# Opticalpulsesensor1.net
KiCad netlist of a schematic drawn in EAGLE
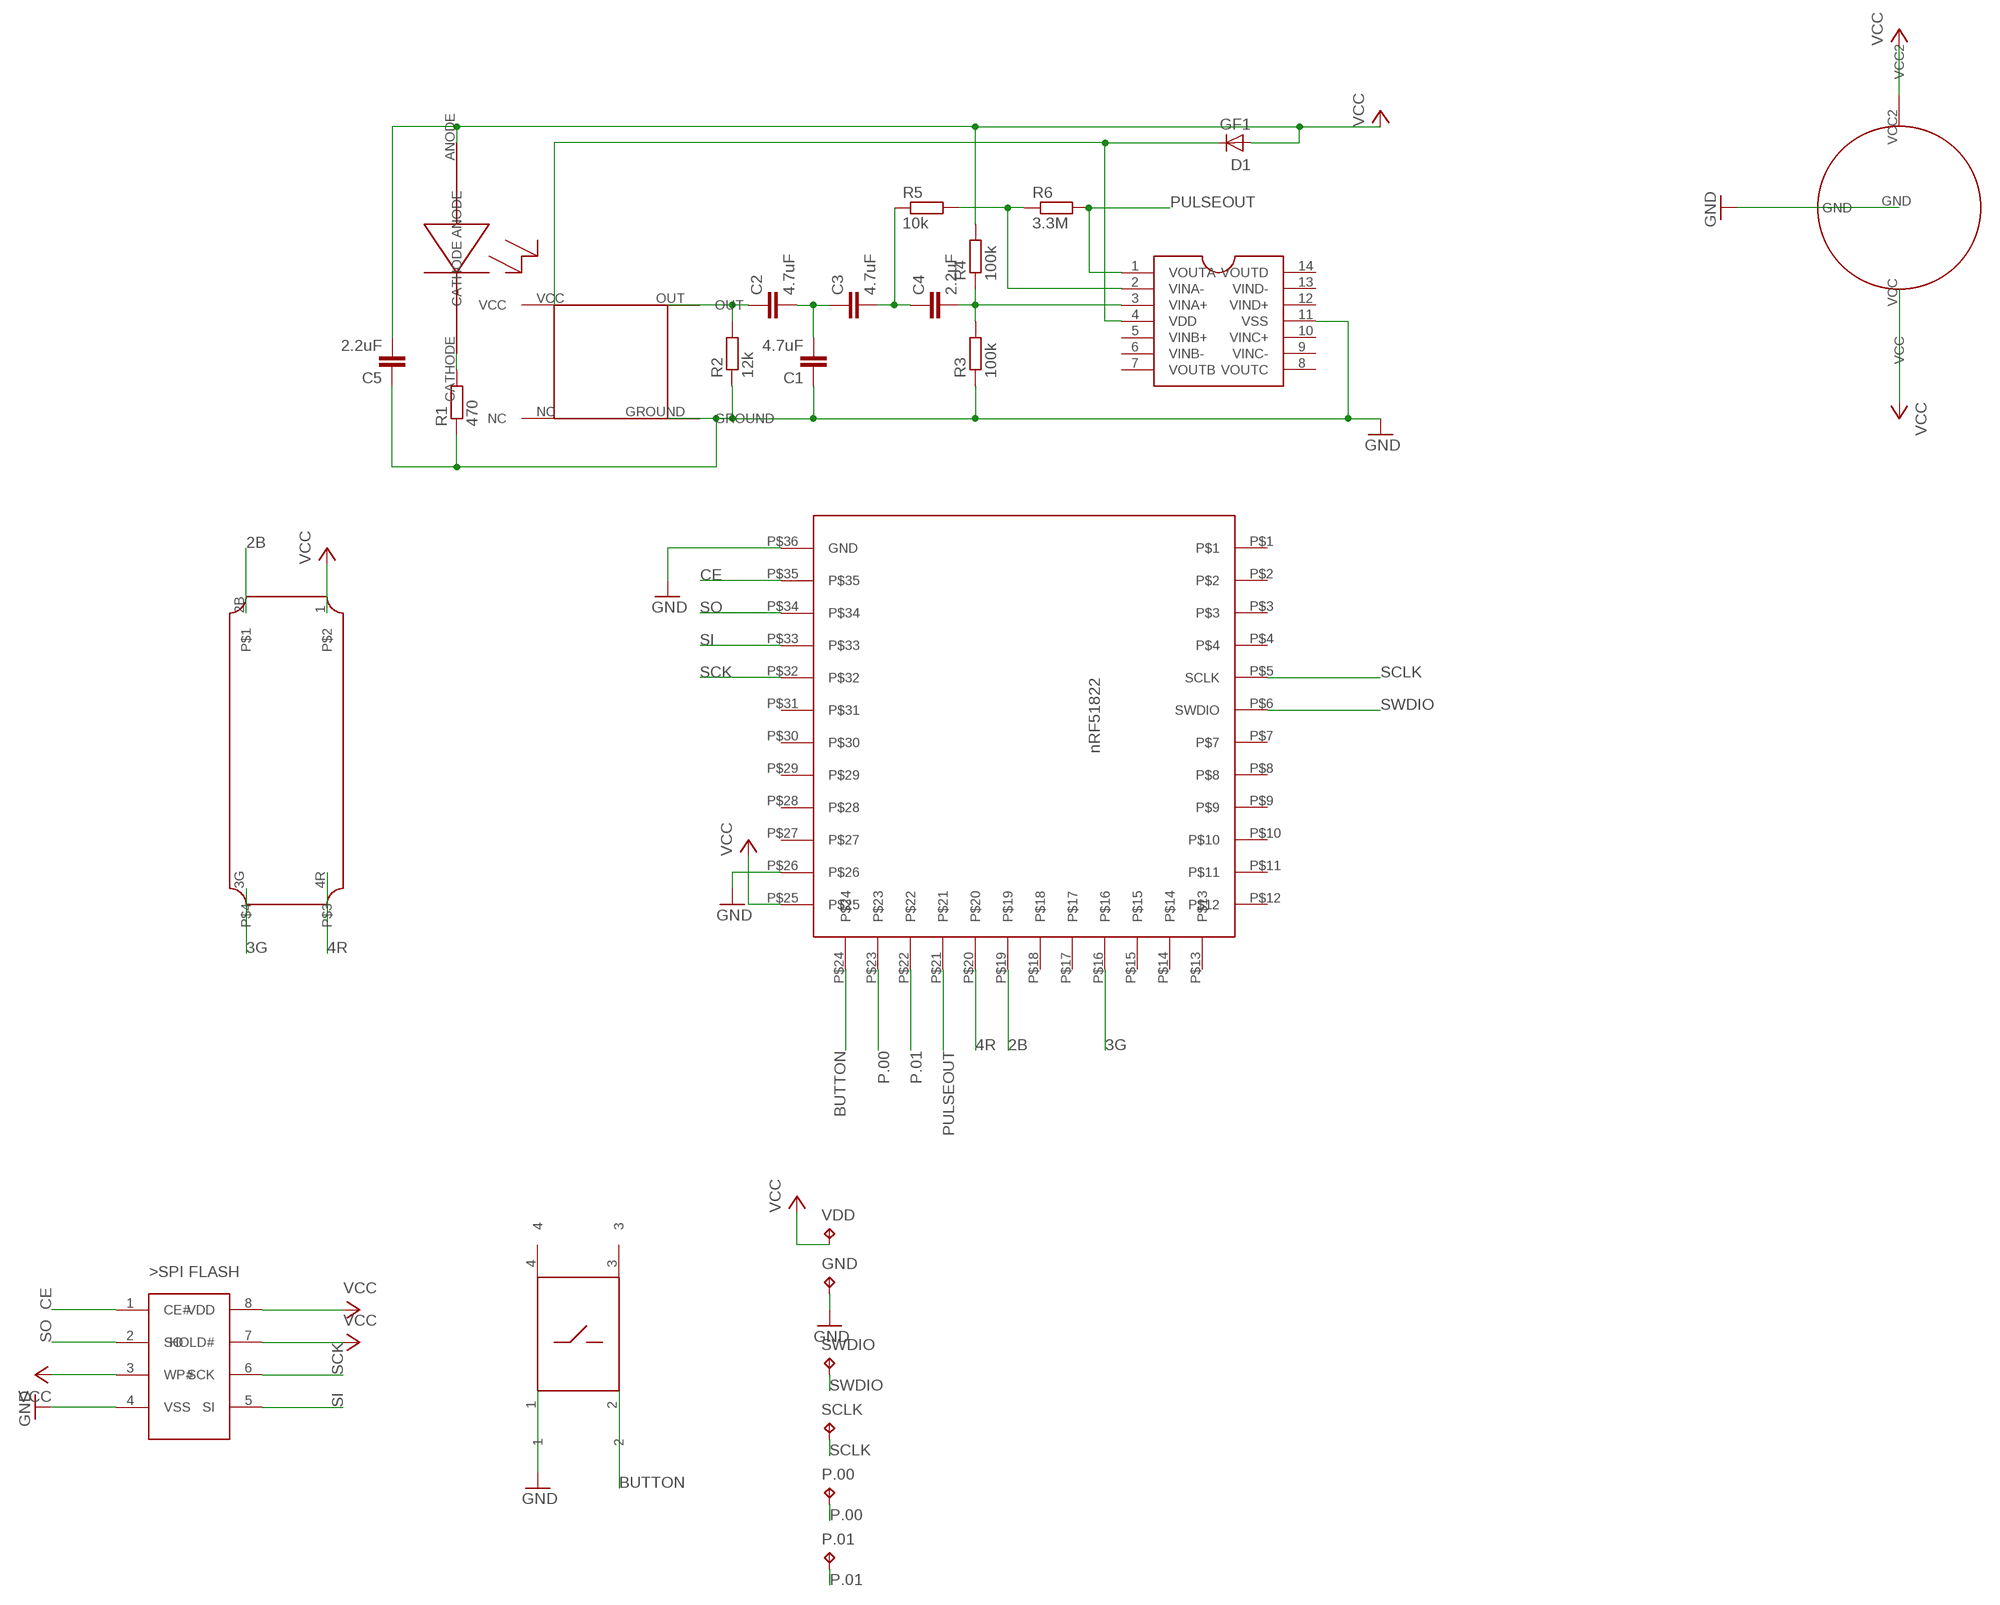
[diagram p0: schematic, sheet 1]

(export (version "E")
  (design (tool "Eeschema 10.0.6"))
  (components
    (comp (ref "C1")
      (value "4.7uF")
      (footprint "eagle-import:C0805")
      (libsource (lib "eagle-import") (part "C-EUC0805"))
    )
    (comp (ref "C2")
      (value "4.7uF")
      (footprint "eagle-import:C0805")
      (libsource (lib "eagle-import") (part "C-EUC0805"))
    )
    (comp (ref "C3")
      (value "4.7uF")
      (footprint "eagle-import:C0805")
      (libsource (lib "eagle-import") (part "C-EUC0805"))
    )
    (comp (ref "C4")
      (value "2.2uF")
      (footprint "eagle-import:C0805")
      (libsource (lib "eagle-import") (part "C-EUC0805"))
    )
    (comp (ref "C5")
      (value "2.2uF")
      (footprint "eagle-import:C0805")
      (libsource (lib "eagle-import") (part "C-EUC0805"))
    )
    (comp (ref "D1")
      (value "GF1")
      (footprint "eagle-import:SMA-DO214AC")
      (libsource (lib "eagle-import") (part "GF1"))
    )
    (comp (ref "GND")
      (value "TPTP09SQ")
      (footprint "eagle-import:TP09SQ")
      (libsource (lib "eagle-import") (part "TPTP09SQ"))
    )
    (comp (ref "P.00")
      (value "TPTP09SQ")
      (footprint "eagle-import:TP09SQ")
      (libsource (lib "eagle-import") (part "TPTP09SQ"))
    )
    (comp (ref "P.01")
      (value "TPTP09SQ")
      (footprint "eagle-import:TP09SQ")
      (libsource (lib "eagle-import") (part "TPTP09SQ"))
    )
    (comp (ref "R1")
      (value "470")
      (footprint "eagle-import:M0805")
      (libsource (lib "eagle-import") (part "R-EU_M0805"))
    )
    (comp (ref "R2")
      (value "12k")
      (footprint "eagle-import:M0805")
      (libsource (lib "eagle-import") (part "R-EU_M0805"))
    )
    (comp (ref "R3")
      (value "100k")
      (footprint "eagle-import:M0805")
      (libsource (lib "eagle-import") (part "R-EU_M0805"))
    )
    (comp (ref "R4")
      (value "100k")
      (footprint "eagle-import:M0805")
      (libsource (lib "eagle-import") (part "R-EU_M0805"))
    )
    (comp (ref "R5")
      (value "10k")
      (footprint "eagle-import:M0805")
      (libsource (lib "eagle-import") (part "R-EU_M0805"))
    )
    (comp (ref "R6")
      (value "3.3M")
      (footprint "eagle-import:M0805")
      (libsource (lib "eagle-import") (part "R-EU_M0805"))
    )
    (comp (ref "SCLK")
      (value "TPTP09SQ")
      (footprint "eagle-import:TP09SQ")
      (libsource (lib "eagle-import") (part "TPTP09SQ"))
    )
    (comp (ref "SWDIO")
      (value "TPTP09SQ")
      (footprint "eagle-import:TP09SQ")
      (libsource (lib "eagle-import") (part "TPTP09SQ"))
    )
    (comp (ref "U$1")
      (value "LIGHTSENSOR")
      (footprint "eagle-import:LIGHTSENSOR")
      (libsource (lib "eagle-import") (part "LIGHTSENSOR"))
    )
    (comp (ref "U$2")
      (value "OPAMP")
      (footprint "eagle-import:TSSOP-14")
      (libsource (lib "eagle-import") (part "OPAMP"))
    )
    (comp (ref "U$3")
      (value "GREENLED")
      (footprint "eagle-import:GREENLED")
      (libsource (lib "eagle-import") (part "GREENLED"))
    )
    (comp (ref "U$4")
      (value "BATTERY")
      (footprint "eagle-import:BATTERY")
      (libsource (lib "eagle-import") (part "BATTERY"))
    )
    (comp (ref "U$5")
      (value "NRF51822")
      (footprint "eagle-import:NRF51822")
      (libsource (lib "eagle-import") (part "NRF51822"))
    )
    (comp (ref "U$6")
      (value "BUTTON1")
      (footprint "eagle-import:BUTTON1")
      (libsource (lib "eagle-import") (part "BUTTON1"))
    )
    (comp (ref "U$7")
      (value "RGB")
      (footprint "eagle-import:RGB")
      (libsource (lib "eagle-import") (part "RGB"))
    )
    (comp (ref "U$8")
      (value "SPI_FLASH")
      (footprint "eagle-import:SOIC-8")
      (libsource (lib "eagle-import") (part "SPI_FLASH"))
    )
    (comp (ref "VDD")
      (value "TPTP09SQ")
      (footprint "eagle-import:TP09SQ")
      (libsource (lib "eagle-import") (part "TPTP09SQ"))
    )
  )
  (nets
    (net (code "1") (name "/2B") (class "Default")
      (node (ref "U$5") (pin "P$19") (pinfunction "P$19_P$19") (pintype "bidirectional"))
      (node (ref "U$7") (pin "2B") (pinfunction "P$1_2B") (pintype "bidirectional"))
    )
    (net (code "2") (name "/3G") (class "Default")
      (node (ref "U$5") (pin "P$16") (pinfunction "P$16_P$16") (pintype "bidirectional"))
      (node (ref "U$7") (pin "3G") (pinfunction "P$4_3G") (pintype "bidirectional"))
    )
    (net (code "3") (name "/4R") (class "Default")
      (node (ref "U$5") (pin "P$20") (pinfunction "P$20_P$20") (pintype "bidirectional"))
    )
    (net (code "4") (name "/BUTTON") (class "Default")
      (node (ref "U$5") (pin "P$24") (pinfunction "P$24_P$24") (pintype "bidirectional"))
      (node (ref "U$6") (pin "2") (pinfunction "2_2") (pintype "bidirectional"))
    )
    (net (code "5") (name "/CE") (class "Default")
      (node (ref "U$5") (pin "P$35") (pinfunction "P$35_P$35") (pintype "bidirectional"))
      (node (ref "U$8") (pin "1") (pinfunction "CE#_1") (pintype "bidirectional"))
    )
    (net (code "6") (name "/P.00") (class "Default")
      (node (ref "P.00") (pin "TP") (pinfunction "TP_TP") (pintype "input"))
      (node (ref "U$5") (pin "P$23") (pinfunction "P$23_P$23") (pintype "bidirectional"))
    )
    (net (code "7") (name "/P.01") (class "Default")
      (node (ref "P.01") (pin "TP") (pinfunction "TP_TP") (pintype "input"))
      (node (ref "U$5") (pin "P$22") (pinfunction "P$22_P$22") (pintype "bidirectional"))
    )
    (net (code "8") (name "/PULSEOUT") (class "Default")
      (node (ref "R6") (pin "2") (pinfunction "2_2") (pintype "passive"))
      (node (ref "U$2") (pin "1") (pinfunction "VOUTA_1") (pintype "bidirectional"))
      (node (ref "U$5") (pin "P$21") (pinfunction "P$21_P$21") (pintype "bidirectional"))
    )
    (net (code "9") (name "/SCK") (class "Default")
      (node (ref "U$5") (pin "P$32") (pinfunction "P$32_P$32") (pintype "bidirectional"))
      (node (ref "U$8") (pin "6") (pinfunction "SCK_6") (pintype "bidirectional"))
    )
    (net (code "10") (name "/SCLK") (class "Default")
      (node (ref "SCLK") (pin "TP") (pinfunction "TP_TP") (pintype "input"))
      (node (ref "U$5") (pin "P$5") (pinfunction "SCLK_P$5") (pintype "bidirectional"))
    )
    (net (code "11") (name "/SI") (class "Default")
      (node (ref "U$5") (pin "P$33") (pinfunction "P$33_P$33") (pintype "bidirectional"))
      (node (ref "U$8") (pin "5") (pinfunction "SI_5") (pintype "bidirectional"))
    )
    (net (code "12") (name "/SO") (class "Default")
      (node (ref "U$5") (pin "P$34") (pinfunction "P$34_P$34") (pintype "bidirectional"))
      (node (ref "U$8") (pin "2") (pinfunction "SO_2") (pintype "bidirectional"))
    )
    (net (code "13") (name "/SWDIO") (class "Default")
      (node (ref "SWDIO") (pin "TP") (pinfunction "TP_TP") (pintype "input"))
      (node (ref "U$5") (pin "P$6") (pinfunction "SWDIO_P$6") (pintype "bidirectional"))
    )
    (net (code "14") (name "GND") (class "Default")
      (node (ref "C1") (pin "1") (pinfunction "1_1") (pintype "passive"))
      (node (ref "C5") (pin "1") (pinfunction "1_1") (pintype "passive"))
      (node (ref "GND") (pin "TP") (pinfunction "TP_TP") (pintype "input"))
      (node (ref "R1") (pin "1") (pinfunction "1_1") (pintype "passive"))
      (node (ref "R2") (pin "1") (pinfunction "1_1") (pintype "passive"))
      (node (ref "R3") (pin "1") (pinfunction "1_1") (pintype "passive"))
      (node (ref "U$1") (pin "GROUND") (pinfunction "GROUND_GROUND") (pintype "bidirectional"))
      (node (ref "U$2") (pin "11") (pinfunction "VSS_11") (pintype "bidirectional"))
      (node (ref "U$4") (pin "GND") (pinfunction "GND_GND") (pintype "bidirectional"))
      (node (ref "U$5") (pin "P$26") (pinfunction "P$26_P$26") (pintype "bidirectional"))
      (node (ref "U$5") (pin "P$36") (pinfunction "GND_P$36") (pintype "bidirectional"))
      (node (ref "U$6") (pin "1") (pinfunction "1_1") (pintype "bidirectional"))
      (node (ref "U$8") (pin "4") (pinfunction "VSS_4") (pintype "bidirectional"))
    )
    (net (code "15") (name "Net-(C1-Pad2)") (class "Default")
      (node (ref "C1") (pin "2") (pinfunction "2_2") (pintype "passive"))
      (node (ref "C2") (pin "2") (pinfunction "2_2") (pintype "passive"))
      (node (ref "C3") (pin "1") (pinfunction "1_1") (pintype "passive"))
    )
    (net (code "16") (name "Net-(C2-Pad1)") (class "Default")
      (node (ref "C2") (pin "1") (pinfunction "1_1") (pintype "passive"))
      (node (ref "R2") (pin "2") (pinfunction "2_2") (pintype "passive"))
      (node (ref "U$1") (pin "OUT") (pinfunction "OUT_OUT") (pintype "bidirectional"))
    )
    (net (code "17") (name "Net-(C3-Pad2)") (class "Default")
      (node (ref "C3") (pin "2") (pinfunction "2_2") (pintype "passive"))
      (node (ref "C4") (pin "1") (pinfunction "1_1") (pintype "passive"))
      (node (ref "R5") (pin "1") (pinfunction "1_1") (pintype "passive"))
    )
    (net (code "18") (name "Net-(D1-C)") (class "Default")
      (node (ref "D1") (pin "K") (pinfunction "C_K") (pintype "passive"))
      (node (ref "U$1") (pin "VCC") (pinfunction "VCC_VCC") (pintype "bidirectional"))
      (node (ref "U$2") (pin "4") (pinfunction "VDD_4") (pintype "bidirectional"))
    )
    (net (code "19") (name "Net-(R1-Pad2)") (class "Default")
      (node (ref "R1") (pin "2") (pinfunction "2_2") (pintype "passive"))
      (node (ref "U$3") (pin "CATHODE") (pinfunction "CATHODE_CATHODE") (pintype "bidirectional"))
    )
    (net (code "20") (name "Net-(U$2-VINA+)") (class "Default")
      (node (ref "C4") (pin "2") (pinfunction "2_2") (pintype "passive"))
      (node (ref "R3") (pin "2") (pinfunction "2_2") (pintype "passive"))
      (node (ref "R4") (pin "1") (pinfunction "1_1") (pintype "passive"))
      (node (ref "U$2") (pin "3") (pinfunction "VINA+_3") (pintype "bidirectional"))
    )
    (net (code "21") (name "Net-(U$2-VINA-)") (class "Default")
      (node (ref "R5") (pin "2") (pinfunction "2_2") (pintype "passive"))
      (node (ref "R6") (pin "1") (pinfunction "1_1") (pintype "passive"))
      (node (ref "U$2") (pin "2") (pinfunction "VINA-_2") (pintype "bidirectional"))
    )
    (net (code "22") (name "VCC") (class "Default")
      (node (ref "C5") (pin "2") (pinfunction "2_2") (pintype "passive"))
      (node (ref "D1") (pin "A") (pinfunction "A_A") (pintype "passive"))
      (node (ref "R4") (pin "2") (pinfunction "2_2") (pintype "passive"))
      (node (ref "U$3") (pin "ANODE") (pinfunction "ANODE_ANODE") (pintype "bidirectional"))
      (node (ref "U$4") (pin "VCC") (pinfunction "VCC_VCC") (pintype "bidirectional"))
      (node (ref "U$5") (pin "P$25") (pinfunction "P$25_P$25") (pintype "bidirectional"))
      (node (ref "U$7") (pin "1") (pinfunction "P$2_1") (pintype "bidirectional"))
      (node (ref "U$8") (pin "3") (pinfunction "WP#_3") (pintype "bidirectional"))
      (node (ref "U$8") (pin "7") (pinfunction "HOLD#_7") (pintype "bidirectional"))
      (node (ref "U$8") (pin "8") (pinfunction "VDD_8") (pintype "bidirectional"))
      (node (ref "VDD") (pin "TP") (pinfunction "TP_TP") (pintype "input"))
    )
    (net (code "23") (name "unconnected-(U$1-PadNC)") (class "Default")
      (node (ref "U$1") (pin "NC") (pinfunction "NC_NC") (pintype "bidirectional"))
    )
    (net (code "24") (name "unconnected-(U$2-VINB+-Pad5)") (class "Default")
      (node (ref "U$2") (pin "5") (pinfunction "VINB+_5") (pintype "bidirectional"))
    )
    (net (code "25") (name "unconnected-(U$2-VINB--Pad6)") (class "Default")
      (node (ref "U$2") (pin "6") (pinfunction "VINB-_6") (pintype "bidirectional"))
    )
    (net (code "26") (name "unconnected-(U$2-VINC+-Pad10)") (class "Default")
      (node (ref "U$2") (pin "10") (pinfunction "VINC+_10") (pintype "bidirectional"))
    )
    (net (code "27") (name "unconnected-(U$2-VINC--Pad9)") (class "Default")
      (node (ref "U$2") (pin "9") (pinfunction "VINC-_9") (pintype "bidirectional"))
    )
    (net (code "28") (name "unconnected-(U$2-VIND+-Pad12)") (class "Default")
      (node (ref "U$2") (pin "12") (pinfunction "VIND+_12") (pintype "bidirectional"))
    )
    (net (code "29") (name "unconnected-(U$2-VIND--Pad13)") (class "Default")
      (node (ref "U$2") (pin "13") (pinfunction "VIND-_13") (pintype "bidirectional"))
    )
    (net (code "30") (name "unconnected-(U$2-VOUTB-Pad7)") (class "Default")
      (node (ref "U$2") (pin "7") (pinfunction "VOUTB_7") (pintype "bidirectional"))
    )
    (net (code "31") (name "unconnected-(U$2-VOUTC-Pad8)") (class "Default")
      (node (ref "U$2") (pin "8") (pinfunction "VOUTC_8") (pintype "bidirectional"))
    )
    (net (code "32") (name "unconnected-(U$2-VOUTD-Pad14)") (class "Default")
      (node (ref "U$2") (pin "14") (pinfunction "VOUTD_14") (pintype "bidirectional"))
    )
    (net (code "33") (name "unconnected-(U$4-PadVCC2)") (class "Default")
      (node (ref "U$4") (pin "VCC2") (pinfunction "VCC2_VCC2") (pintype "bidirectional"))
    )
    (net (code "34") (name "unconnected-(U$5-PadP$1)") (class "Default")
      (node (ref "U$5") (pin "P$1") (pinfunction "P$1_P$1") (pintype "bidirectional"))
    )
    (net (code "35") (name "unconnected-(U$5-PadP$2)") (class "Default")
      (node (ref "U$5") (pin "P$2") (pinfunction "P$2_P$2") (pintype "bidirectional"))
    )
    (net (code "36") (name "unconnected-(U$5-PadP$3)") (class "Default")
      (node (ref "U$5") (pin "P$3") (pinfunction "P$3_P$3") (pintype "bidirectional"))
    )
    (net (code "37") (name "unconnected-(U$5-PadP$4)") (class "Default")
      (node (ref "U$5") (pin "P$4") (pinfunction "P$4_P$4") (pintype "bidirectional"))
    )
    (net (code "38") (name "unconnected-(U$5-PadP$7)") (class "Default")
      (node (ref "U$5") (pin "P$7") (pinfunction "P$7_P$7") (pintype "bidirectional"))
    )
    (net (code "39") (name "unconnected-(U$5-PadP$8)") (class "Default")
      (node (ref "U$5") (pin "P$8") (pinfunction "P$8_P$8") (pintype "bidirectional"))
    )
    (net (code "40") (name "unconnected-(U$5-PadP$9)") (class "Default")
      (node (ref "U$5") (pin "P$9") (pinfunction "P$9_P$9") (pintype "bidirectional"))
    )
    (net (code "41") (name "unconnected-(U$5-PadP$10)") (class "Default")
      (node (ref "U$5") (pin "P$10") (pinfunction "P$10_P$10") (pintype "bidirectional"))
    )
    (net (code "42") (name "unconnected-(U$5-PadP$11)") (class "Default")
      (node (ref "U$5") (pin "P$11") (pinfunction "P$11_P$11") (pintype "bidirectional"))
    )
    (net (code "43") (name "unconnected-(U$5-PadP$12)") (class "Default")
      (node (ref "U$5") (pin "P$12") (pinfunction "P$12_P$12") (pintype "bidirectional"))
    )
    (net (code "44") (name "unconnected-(U$5-PadP$13)") (class "Default")
      (node (ref "U$5") (pin "P$13") (pinfunction "P$13_P$13") (pintype "bidirectional"))
    )
    (net (code "45") (name "unconnected-(U$5-PadP$14)") (class "Default")
      (node (ref "U$5") (pin "P$14") (pinfunction "P$14_P$14") (pintype "bidirectional"))
    )
    (net (code "46") (name "unconnected-(U$5-PadP$15)") (class "Default")
      (node (ref "U$5") (pin "P$15") (pinfunction "P$15_P$15") (pintype "bidirectional"))
    )
    (net (code "47") (name "unconnected-(U$5-PadP$17)") (class "Default")
      (node (ref "U$5") (pin "P$17") (pinfunction "P$17_P$17") (pintype "bidirectional"))
    )
    (net (code "48") (name "unconnected-(U$5-PadP$18)") (class "Default")
      (node (ref "U$5") (pin "P$18") (pinfunction "P$18_P$18") (pintype "bidirectional"))
    )
    (net (code "49") (name "unconnected-(U$5-PadP$27)") (class "Default")
      (node (ref "U$5") (pin "P$27") (pinfunction "P$27_P$27") (pintype "bidirectional"))
    )
    (net (code "50") (name "unconnected-(U$5-PadP$28)") (class "Default")
      (node (ref "U$5") (pin "P$28") (pinfunction "P$28_P$28") (pintype "bidirectional"))
    )
    (net (code "51") (name "unconnected-(U$5-PadP$29)") (class "Default")
      (node (ref "U$5") (pin "P$29") (pinfunction "P$29_P$29") (pintype "bidirectional"))
    )
    (net (code "52") (name "unconnected-(U$5-PadP$30)") (class "Default")
      (node (ref "U$5") (pin "P$30") (pinfunction "P$30_P$30") (pintype "bidirectional"))
    )
    (net (code "53") (name "unconnected-(U$5-PadP$31)") (class "Default")
      (node (ref "U$5") (pin "P$31") (pinfunction "P$31_P$31") (pintype "bidirectional"))
    )
    (net (code "54") (name "unconnected-(U$6-Pad3)") (class "Default")
      (node (ref "U$6") (pin "3") (pinfunction "3_3") (pintype "bidirectional"))
    )
    (net (code "55") (name "unconnected-(U$6-Pad4)") (class "Default")
      (node (ref "U$6") (pin "4") (pinfunction "4_4") (pintype "bidirectional"))
    )
    (net (code "56") (name "unconnected-(U$7-P$3-Pad4R)") (class "Default")
      (node (ref "U$7") (pin "4R") (pinfunction "P$3_4R") (pintype "bidirectional"))
    )
  )
)
